# ABoatMon.net
KiCad netlist of a schematic drawn in EAGLE
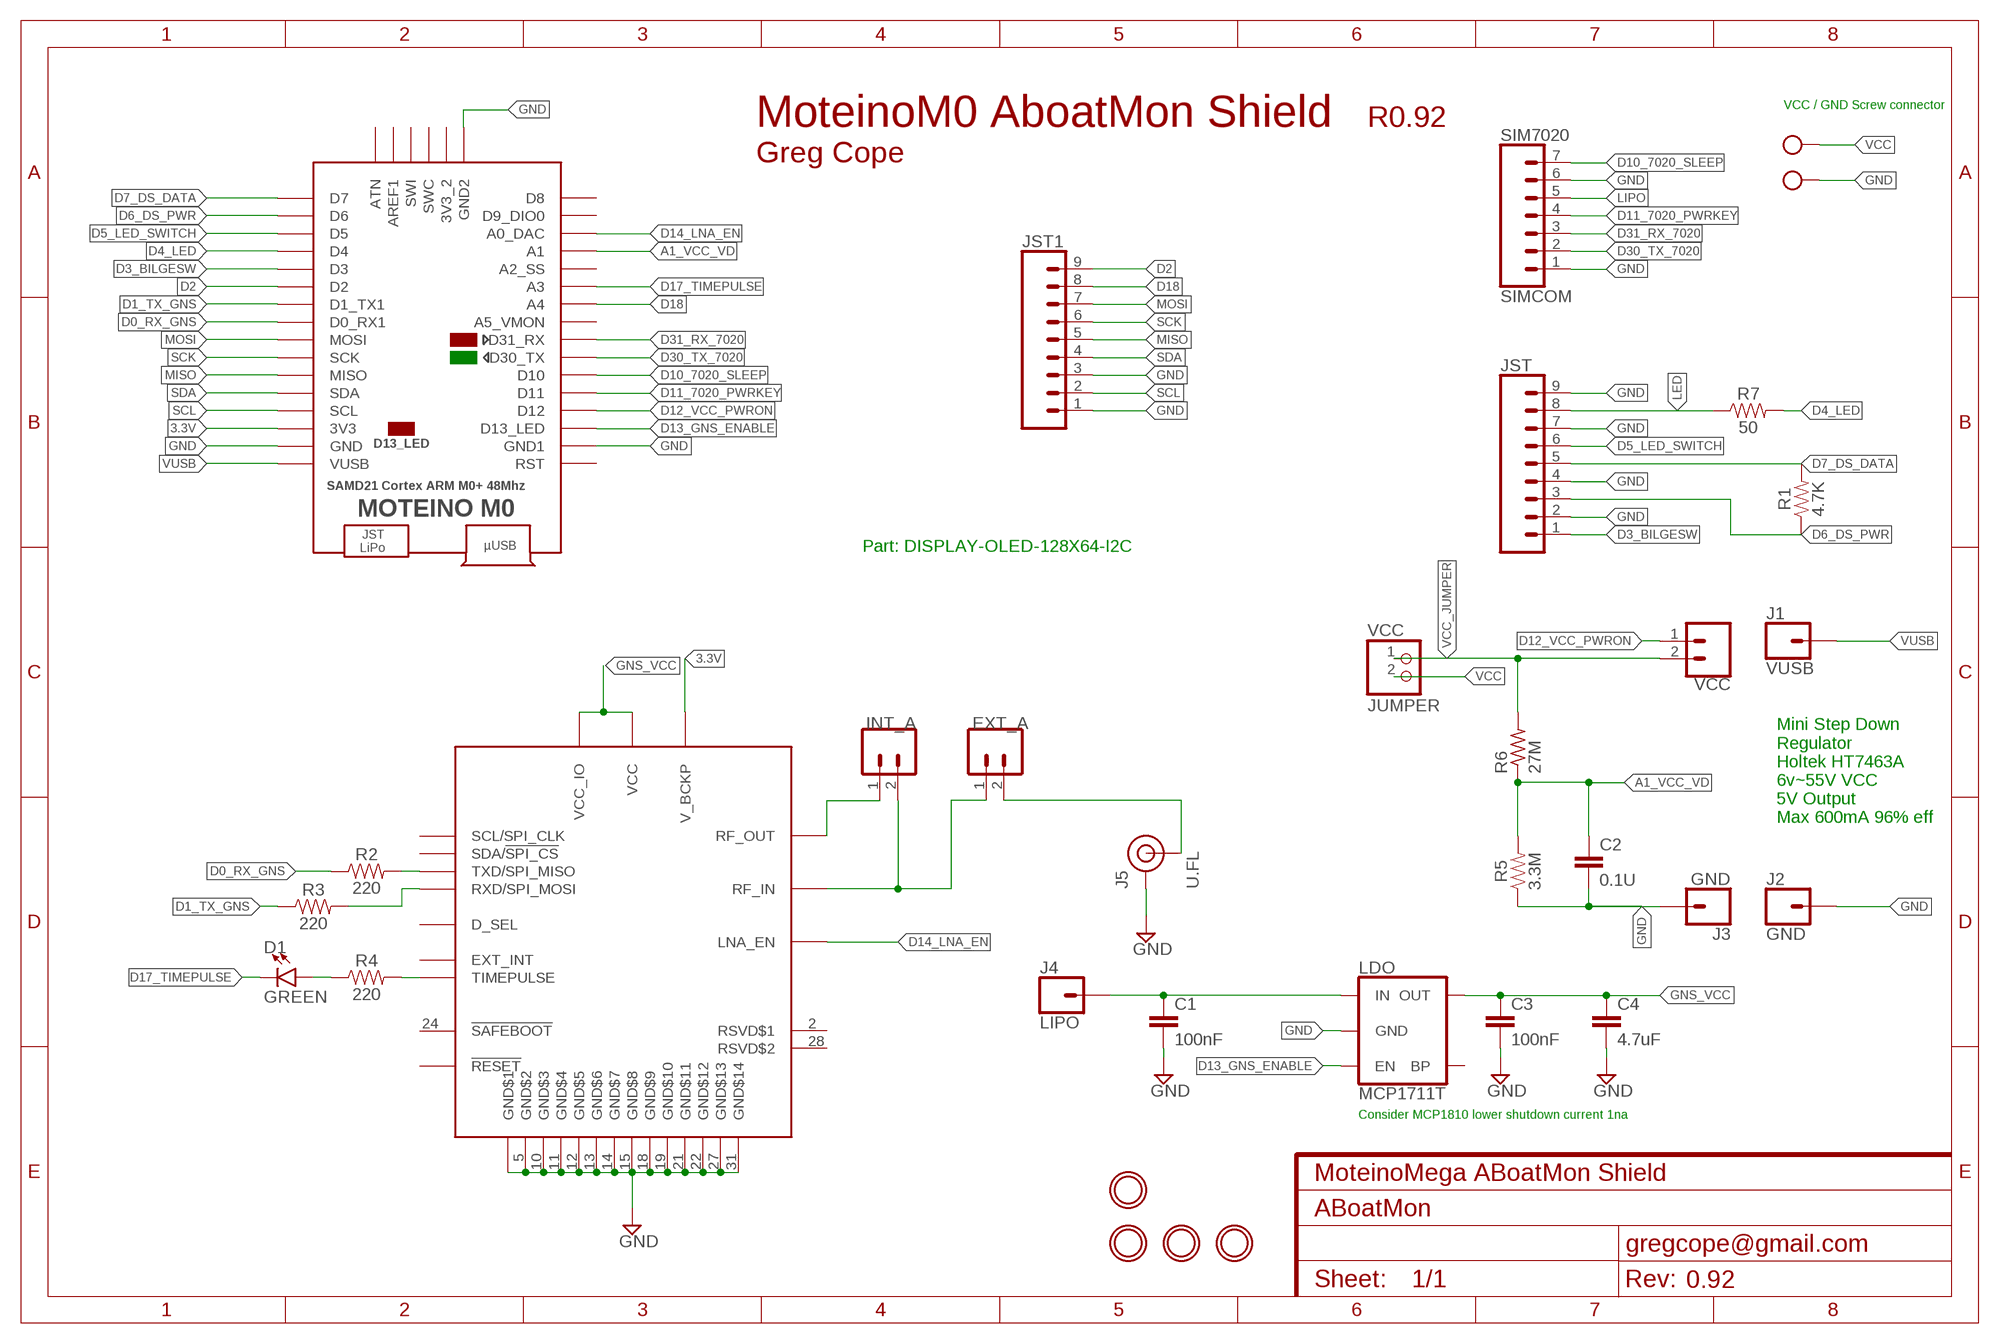
[diagram p0: schematic, sheet 1]

(export (version "E")
  (design (tool "Eeschema 10.0.6"))
  (components
    (comp (ref "C1")
      (value "100nF")
      (footprint "eagle-import:0603")
      (libsource (lib "eagle-import") (part "SparkFun-Capacitors_510_0.1UF-0603-25V-5%"))
    )
    (comp (ref "C2")
      (value "0.1U")
      (footprint "eagle-import:CAP-PTH-SMALL-KIT")
      (libsource (lib "eagle-import") (part "0.1UF-KIT-EZ-50V-20%"))
    )
    (comp (ref "C3")
      (value "100nF")
      (footprint "eagle-import:0603")
      (libsource (lib "eagle-import") (part "SparkFun-Capacitors_510_0.1UF-0603-25V-5%"))
    )
    (comp (ref "C4")
      (value "4.7uF")
      (footprint "eagle-import:0603")
      (libsource (lib "eagle-import") (part "4.7UF0603"))
    )
    (comp (ref "D1")
      (value "GREEN")
      (footprint "eagle-import:LED-0603")
      (libsource (lib "eagle-import") (part "LED-GREEN0603"))
    )
    (comp (ref "ENABLE")
      (value "VCC")
      (footprint "eagle-import:1X02")
      (libsource (lib "eagle-import") (part "CONN_02"))
    )
    (comp (ref "EXT_A")
      (value "CONN_02")
      (footprint "eagle-import:1X02")
      (libsource (lib "eagle-import") (part "SparkFun-Connectors_513_CONN_02"))
    )
    (comp (ref "GND")
      (value "MOUNTINGHOLE2.5")
      (footprint "eagle-import:MOUNTINGHOLE_2.5_PLATED")
      (libsource (lib "eagle-import") (part "MOUNTINGHOLE2.5"))
    )
    (comp (ref "INT_A")
      (value "CONN_02")
      (footprint "eagle-import:1X02")
      (libsource (lib "eagle-import") (part "SparkFun-Connectors_513_CONN_02"))
    )
    (comp (ref "J1")
      (value "VUSB")
      (footprint "eagle-import:1X01")
      (libsource (lib "eagle-import") (part "CONN_01"))
    )
    (comp (ref "J2")
      (value "GND")
      (footprint "eagle-import:1X01")
      (libsource (lib "eagle-import") (part "CONN_01"))
    )
    (comp (ref "J3")
      (value "GND")
      (footprint "eagle-import:1X01")
      (libsource (lib "eagle-import") (part "CONN_01"))
    )
    (comp (ref "J4")
      (value "LIPO")
      (footprint "eagle-import:1X01")
      (libsource (lib "eagle-import") (part "CONN_01"))
    )
    (comp (ref "J5")
      (value "U.FL")
      (footprint "eagle-import:U.FL")
      (libsource (lib "eagle-import") (part "U.FL2PIN"))
    )
    (comp (ref "JST")
      (value "CONN_09")
      (footprint "eagle-import:1X09")
      (libsource (lib "eagle-import") (part "CONN_09"))
    )
    (comp (ref "JST1")
      (value "CONN_09")
      (footprint "eagle-import:1X09")
      (libsource (lib "eagle-import") (part "CONN_09"))
    )
    (comp (ref "LDO")
      (value "MCP1711T")
      (footprint "eagle-import:SOT23-5")
      (libsource (lib "eagle-import") (part "V_REG_SPX3819-SOT23-5"))
    )
    (comp (ref "R1")
      (value "4.7K")
      (footprint "eagle-import:AXIAL-0.3")
      (libsource (lib "eagle-import") (part "1KOHM-HORIZ-1/4W-1%"))
    )
    (comp (ref "R2")
      (value "220")
      (footprint "eagle-import:0603")
      (libsource (lib "eagle-import") (part "220OHM-0603-1/10W-1%"))
    )
    (comp (ref "R3")
      (value "220")
      (footprint "eagle-import:0603")
      (libsource (lib "eagle-import") (part "220OHM-0603-1/10W-1%"))
    )
    (comp (ref "R4")
      (value "220")
      (footprint "eagle-import:0603")
      (libsource (lib "eagle-import") (part "220OHM-0603-1/10W-1%"))
    )
    (comp (ref "R5")
      (value "3.3M")
      (footprint "eagle-import:AXIAL-0.3")
      (libsource (lib "eagle-import") (part "1KOHM-HORIZ-1/4W-1%"))
    )
    (comp (ref "R6")
      (value "27M")
      (footprint "eagle-import:0309_12")
      (libsource (lib "eagle-import") (part "R-US_0309/12"))
    )
    (comp (ref "R7")
      (value "50")
      (footprint "eagle-import:AXIAL-0.3")
      (libsource (lib "eagle-import") (part "1KOHM-HORIZ-1/4W-1%"))
    )
    (comp (ref "SIM7020")
      (value "SIMCOM")
      (footprint "eagle-import:1X07")
      (libsource (lib "eagle-import") (part "CONN_07"))
    )
    (comp (ref "U$3")
      (value "MOUNTINGHOLE2.0")
      (footprint "eagle-import:MOUNTINGHOLE_2.0_PLATED")
      (libsource (lib "eagle-import") (part "MOUNTINGHOLE2.0"))
    )
    (comp (ref "U$5")
      (value "CAM-M8")
      (footprint "eagle-import:CAM-M8")
      (libsource (lib "eagle-import") (part "CAM-M8"))
    )
    (comp (ref "U$6")
      (value "MOTEINO_M0")
      (footprint "eagle-import:MOTEINO_M0")
      (libsource (lib "eagle-import") (part "MOTEINO_M0"))
    )
    (comp (ref "U$7")
      (value "MOUNTINGHOLE2.5")
      (footprint "eagle-import:MOUNTINGHOLE_2.5_PLATED")
      (libsource (lib "eagle-import") (part "MOUNTINGHOLE2.5"))
    )
    (comp (ref "U$9")
      (value "MOUNTINGHOLE2.0")
      (footprint "eagle-import:MOUNTINGHOLE_2.0_PLATED")
      (libsource (lib "eagle-import") (part "MOUNTINGHOLE2.0"))
    )
    (comp (ref "VCC")
      (value "JUMPER")
      (footprint "eagle-import:1X02_ROUND")
      (libsource (lib "eagle-import") (part "HEADER-1X2ROUND"))
    )
    (comp (ref "X1")
      (value "MKDSN1,5/2-5,08")
      (footprint "eagle-import:MKDSN1,5_2-5,08")
      (libsource (lib "eagle-import") (part "MKDSN1,5/2-5,08"))
    )
  )
  (nets
    (net (code "1") (name "3.3V") (class "Default")
      (node (ref "U$5") (pin "8") (pinfunction "V_BCKP_8") (pintype "power_in"))
      (node (ref "U$6") (pin "3V3") (pinfunction "3V3_3V3") (pintype "bidirectional"))
    )
    (net (code "2") (name "A1_VCC_VD") (class "Default")
      (node (ref "C2") (pin "1") (pinfunction "1_1") (pintype "passive"))
      (node (ref "R5") (pin "P$2") (pinfunction "2_P$2") (pintype "passive"))
      (node (ref "R6") (pin "1") (pinfunction "1_1") (pintype "passive"))
      (node (ref "U$6") (pin "A1") (pinfunction "A1_A1") (pintype "bidirectional"))
    )
    (net (code "3") (name "D0_RX_GNS") (class "Default")
      (node (ref "R2") (pin "1") (pinfunction "1_1") (pintype "passive"))
      (node (ref "U$6") (pin "D0_RX1") (pinfunction "D0_RX1_D0_RX1") (pintype "bidirectional"))
    )
    (net (code "4") (name "D1_TX_GNS") (class "Default")
      (node (ref "R3") (pin "1") (pinfunction "1_1") (pintype "passive"))
      (node (ref "U$6") (pin "D1_TX1") (pinfunction "D1_TX1_D1_TX1") (pintype "bidirectional"))
    )
    (net (code "5") (name "D2") (class "Default")
      (node (ref "JST1") (pin "9") (pinfunction "9_9") (pintype "passive"))
      (node (ref "U$6") (pin "D2") (pinfunction "D2_D2") (pintype "bidirectional"))
    )
    (net (code "6") (name "D3_BILGESW") (class "Default")
      (node (ref "JST") (pin "1") (pinfunction "1_1") (pintype "passive"))
      (node (ref "U$6") (pin "D3") (pinfunction "D3_D3") (pintype "bidirectional"))
    )
    (net (code "7") (name "D4_LED") (class "Default")
      (node (ref "R7") (pin "P$2") (pinfunction "2_P$2") (pintype "passive"))
      (node (ref "U$6") (pin "D4") (pinfunction "D4_D4") (pintype "bidirectional"))
    )
    (net (code "8") (name "D5_LED_SWITCH") (class "Default")
      (node (ref "JST") (pin "6") (pinfunction "6_6") (pintype "passive"))
      (node (ref "U$6") (pin "D5") (pinfunction "D5_D5") (pintype "bidirectional"))
    )
    (net (code "9") (name "D6_DS_PWR") (class "Default")
      (node (ref "JST") (pin "3") (pinfunction "3_3") (pintype "passive"))
      (node (ref "R1") (pin "P$1") (pinfunction "1_P$1") (pintype "passive"))
      (node (ref "U$6") (pin "D6") (pinfunction "D6_D6") (pintype "bidirectional"))
    )
    (net (code "10") (name "D7_DS_DATA") (class "Default")
      (node (ref "JST") (pin "5") (pinfunction "5_5") (pintype "passive"))
      (node (ref "R1") (pin "P$2") (pinfunction "2_P$2") (pintype "passive"))
      (node (ref "U$6") (pin "D7") (pinfunction "D7_D7") (pintype "bidirectional"))
    )
    (net (code "11") (name "D10_7020_SLEEP") (class "Default")
      (node (ref "SIM7020") (pin "7") (pinfunction "7_7") (pintype "passive"))
      (node (ref "U$6") (pin "D10") (pinfunction "D10_D10") (pintype "bidirectional"))
    )
    (net (code "12") (name "D11_7020_PWRKEY") (class "Default")
      (node (ref "SIM7020") (pin "4") (pinfunction "4_4") (pintype "passive"))
      (node (ref "U$6") (pin "D11") (pinfunction "D11_D11") (pintype "bidirectional"))
    )
    (net (code "13") (name "D12_VCC_PWRON") (class "Default")
      (node (ref "ENABLE") (pin "1") (pinfunction "1_1") (pintype "passive"))
      (node (ref "U$6") (pin "D12") (pinfunction "D12_D12") (pintype "bidirectional"))
    )
    (net (code "14") (name "D13_GNS_ENABLE") (class "Default")
      (node (ref "LDO") (pin "3") (pinfunction "EN_3") (pintype "input"))
      (node (ref "U$6") (pin "D13") (pinfunction "D13_LED_D13") (pintype "bidirectional"))
    )
    (net (code "15") (name "D14_LNA_EN") (class "Default")
      (node (ref "U$5") (pin "30") (pinfunction "LNA_EN_30") (pintype "output"))
      (node (ref "U$6") (pin "A0_DAC") (pinfunction "A0_DAC_A0_DAC") (pintype "bidirectional"))
    )
    (net (code "16") (name "D17_TIMEPULSE") (class "Default")
      (node (ref "D1") (pin "C") (pinfunction "C_C") (pintype "passive"))
      (node (ref "U$6") (pin "A3") (pinfunction "A3_A3") (pintype "bidirectional"))
    )
    (net (code "17") (name "D18") (class "Default")
      (node (ref "JST1") (pin "8") (pinfunction "8_8") (pintype "passive"))
      (node (ref "U$6") (pin "A4") (pinfunction "A4_A4") (pintype "bidirectional"))
    )
    (net (code "18") (name "D30_TX_7020") (class "Default")
      (node (ref "SIM7020") (pin "2") (pinfunction "2_2") (pintype "passive"))
      (node (ref "U$6") (pin "D30_TX") (pinfunction "D30_TX_D30_TX") (pintype "bidirectional"))
    )
    (net (code "19") (name "D31_RX_7020") (class "Default")
      (node (ref "SIM7020") (pin "3") (pinfunction "3_3") (pintype "passive"))
      (node (ref "U$6") (pin "D31_RX") (pinfunction "D31_RX_D31_RX") (pintype "bidirectional"))
    )
    (net (code "20") (name "GND") (class "Default")
      (node (ref "C1") (pin "2") (pinfunction "2_2") (pintype "passive"))
      (node (ref "C2") (pin "2") (pinfunction "2_2") (pintype "passive"))
      (node (ref "C3") (pin "2") (pinfunction "2_2") (pintype "passive"))
      (node (ref "C4") (pin "2") (pinfunction "2_2") (pintype "passive"))
      (node (ref "J2") (pin "1") (pinfunction "1_1") (pintype "passive"))
      (node (ref "J3") (pin "1") (pinfunction "1_1") (pintype "passive"))
      (node (ref "J5") (pin "1") (pinfunction "GND_1") (pintype "bidirectional"))
      (node (ref "J5") (pin "2") (pinfunction "GND_2") (pintype "bidirectional"))
      (node (ref "JST") (pin "2") (pinfunction "2_2") (pintype "passive"))
      (node (ref "JST") (pin "4") (pinfunction "4_4") (pintype "passive"))
      (node (ref "JST") (pin "7") (pinfunction "7_7") (pintype "passive"))
      (node (ref "JST") (pin "9") (pinfunction "9_9") (pintype "passive"))
      (node (ref "JST1") (pin "1") (pinfunction "1_1") (pintype "passive"))
      (node (ref "JST1") (pin "3") (pinfunction "3_3") (pintype "passive"))
      (node (ref "LDO") (pin "2") (pinfunction "GND_2") (pintype "input"))
      (node (ref "R5") (pin "P$1") (pinfunction "1_P$1") (pintype "passive"))
      (node (ref "SIM7020") (pin "1") (pinfunction "1_1") (pintype "passive"))
      (node (ref "SIM7020") (pin "6") (pinfunction "6_6") (pintype "passive"))
      (node (ref "U$5") (pin "10") (pinfunction "GND$3_10") (pintype "power_in"))
      (node (ref "U$5") (pin "11") (pinfunction "GND$4_11") (pintype "power_in"))
      (node (ref "U$5") (pin "12") (pinfunction "GND$5_12") (pintype "power_in"))
      (node (ref "U$5") (pin "13") (pinfunction "GND$6_13") (pintype "power_in"))
      (node (ref "U$5") (pin "14") (pinfunction "GND$7_14") (pintype "power_in"))
      (node (ref "U$5") (pin "15") (pinfunction "GND$8_15") (pintype "power_in"))
      (node (ref "U$5") (pin "18") (pinfunction "GND$9_18") (pintype "power_in"))
      (node (ref "U$5") (pin "19") (pinfunction "GND$10_19") (pintype "power_in"))
      (node (ref "U$5") (pin "21") (pinfunction "GND$11_21") (pintype "power_in"))
      (node (ref "U$5") (pin "22") (pinfunction "GND$12_22") (pintype "power_in"))
      (node (ref "U$5") (pin "27") (pinfunction "GND$13_27") (pintype "power_in"))
      (node (ref "U$5") (pin "31") (pinfunction "GND$14_31") (pintype "power_in"))
      (node (ref "U$5") (pin "4") (pinfunction "GND$1_4") (pintype "power_in"))
      (node (ref "U$5") (pin "5") (pinfunction "GND$2_5") (pintype "power_in"))
      (node (ref "U$6") (pin "GND") (pinfunction "GND_GND") (pintype "bidirectional"))
      (node (ref "U$6") (pin "GND_1") (pinfunction "GND1_GND_1") (pintype "bidirectional"))
      (node (ref "U$6") (pin "GND_2") (pinfunction "GND2_GND_2") (pintype "bidirectional"))
      (node (ref "X1") (pin "2") (pinfunction "KL_2") (pintype "passive"))
    )
    (net (code "21") (name "GNS_VCC") (class "Default")
      (node (ref "C3") (pin "1") (pinfunction "1_1") (pintype "passive"))
      (node (ref "C4") (pin "1") (pinfunction "1_1") (pintype "passive"))
      (node (ref "LDO") (pin "5") (pinfunction "OUT_5") (pintype "passive"))
      (node (ref "U$5") (pin "1") (pinfunction "VCC_IO_1") (pintype "power_in"))
      (node (ref "U$5") (pin "9") (pinfunction "VCC_9") (pintype "power_in"))
    )
    (net (code "22") (name "LED") (class "Default")
      (node (ref "JST") (pin "8") (pinfunction "8_8") (pintype "passive"))
      (node (ref "R7") (pin "P$1") (pinfunction "1_P$1") (pintype "passive"))
    )
    (net (code "23") (name "LIPO") (class "Default")
      (node (ref "C1") (pin "1") (pinfunction "1_1") (pintype "passive"))
      (node (ref "J4") (pin "1") (pinfunction "1_1") (pintype "passive"))
      (node (ref "LDO") (pin "1") (pinfunction "IN_1") (pintype "input"))
      (node (ref "SIM7020") (pin "5") (pinfunction "5_5") (pintype "passive"))
    )
    (net (code "24") (name "MISO") (class "Default")
      (node (ref "JST1") (pin "5") (pinfunction "5_5") (pintype "passive"))
      (node (ref "U$6") (pin "MISO") (pinfunction "MISO_MISO") (pintype "bidirectional"))
    )
    (net (code "25") (name "MOSI") (class "Default")
      (node (ref "JST1") (pin "7") (pinfunction "7_7") (pintype "passive"))
      (node (ref "U$6") (pin "MOSI") (pinfunction "MOSI_MOSI") (pintype "bidirectional"))
    )
    (net (code "26") (name "Net-(D1-PadA)") (class "Default")
      (node (ref "D1") (pin "A") (pinfunction "A_A") (pintype "passive"))
      (node (ref "R4") (pin "1") (pinfunction "1_1") (pintype "passive"))
    )
    (net (code "27") (name "Net-(J5-SIGNAL)") (class "Default")
      (node (ref "EXT_A") (pin "2") (pinfunction "2_2") (pintype "passive"))
      (node (ref "J5") (pin "FEED") (pinfunction "SIGNAL_FEED") (pintype "bidirectional"))
    )
    (net (code "28") (name "Net-(U$5-RF_IN)") (class "Default")
      (node (ref "EXT_A") (pin "1") (pinfunction "1_1") (pintype "passive"))
      (node (ref "INT_A") (pin "2") (pinfunction "2_2") (pintype "passive"))
      (node (ref "U$5") (pin "17") (pinfunction "RF_IN_17") (pintype "input"))
    )
    (net (code "29") (name "Net-(U$5-RF_OUT)") (class "Default")
      (node (ref "INT_A") (pin "1") (pinfunction "1_1") (pintype "passive"))
      (node (ref "U$5") (pin "16") (pinfunction "RF_OUT_16") (pintype "output"))
    )
    (net (code "30") (name "Net-(U$5-RXD{slash}SPI_MOSI)") (class "Default")
      (node (ref "R3") (pin "2") (pinfunction "2_2") (pintype "passive"))
      (node (ref "U$5") (pin "26") (pinfunction "RXD/SPI_MOSI_26") (pintype "input"))
    )
    (net (code "31") (name "Net-(U$5-TIMEPULSE)") (class "Default")
      (node (ref "R4") (pin "2") (pinfunction "2_2") (pintype "passive"))
      (node (ref "U$5") (pin "29") (pinfunction "TIMEPULSE_29") (pintype "output"))
    )
    (net (code "32") (name "Net-(U$5-TXD{slash}SPI_MISO)") (class "Default")
      (node (ref "R2") (pin "2") (pinfunction "2_2") (pintype "passive"))
      (node (ref "U$5") (pin "25") (pinfunction "TXD/SPI_MISO_25") (pintype "output"))
    )
    (net (code "33") (name "SCK") (class "Default")
      (node (ref "JST1") (pin "6") (pinfunction "6_6") (pintype "passive"))
      (node (ref "U$6") (pin "SCK") (pinfunction "SCK_SCK") (pintype "bidirectional"))
    )
    (net (code "34") (name "SCL") (class "Default")
      (node (ref "JST1") (pin "2") (pinfunction "2_2") (pintype "passive"))
      (node (ref "U$6") (pin "SCL") (pinfunction "SCL_SCL") (pintype "bidirectional"))
    )
    (net (code "35") (name "SDA") (class "Default")
      (node (ref "JST1") (pin "4") (pinfunction "4_4") (pintype "passive"))
      (node (ref "U$6") (pin "SDA") (pinfunction "SDA_SDA") (pintype "bidirectional"))
    )
    (net (code "36") (name "VCC") (class "Default")
      (node (ref "VCC") (pin "2") (pinfunction "2_2") (pintype "passive"))
      (node (ref "X1") (pin "1") (pinfunction "KL_1") (pintype "passive"))
    )
    (net (code "37") (name "VCC_JUMPER") (class "Default")
      (node (ref "ENABLE") (pin "2") (pinfunction "2_2") (pintype "passive"))
      (node (ref "R6") (pin "2") (pinfunction "2_2") (pintype "passive"))
      (node (ref "VCC") (pin "1") (pinfunction "1_1") (pintype "passive"))
    )
    (net (code "38") (name "VUSB") (class "Default")
      (node (ref "J1") (pin "1") (pinfunction "1_1") (pintype "passive"))
      (node (ref "U$6") (pin "VUSB") (pinfunction "VUSB_VUSB") (pintype "bidirectional"))
    )
    (net (code "39") (name "unconnected-(LDO-BP-Pad4)") (class "Default")
      (node (ref "LDO") (pin "4") (pinfunction "BP_4") (pintype "input"))
    )
    (net (code "40") (name "unconnected-(U$5-D_SEL-Pad20)") (class "Default")
      (node (ref "U$5") (pin "20") (pinfunction "D_SEL_20") (pintype "input"))
    )
    (net (code "41") (name "unconnected-(U$5-EXT_INT-Pad7)") (class "Default")
      (node (ref "U$5") (pin "7") (pinfunction "EXT_INT_7") (pintype "bidirectional"))
    )
    (net (code "42") (name "unconnected-(U$5-RSVD$1-Pad2)") (class "Default")
      (node (ref "U$5") (pin "2") (pinfunction "RSVD$1_2") (pintype "no_connect"))
    )
    (net (code "43") (name "unconnected-(U$5-RSVD$2-Pad28)") (class "Default")
      (node (ref "U$5") (pin "28") (pinfunction "RSVD$2_28") (pintype "no_connect"))
    )
    (net (code "44") (name "unconnected-(U$5-SCL{slash}SPI_CLK-Pad6)") (class "Default")
      (node (ref "U$5") (pin "6") (pinfunction "SCL/SPI_CLK_6") (pintype "input"))
    )
    (net (code "45") (name "unconnected-(U$5-SDA{slash}~{SPI_CS}-Pad3)") (class "Default")
      (node (ref "U$5") (pin "3") (pinfunction "SDA/~{SPI_CS}_3") (pintype "bidirectional"))
    )
    (net (code "46") (name "unconnected-(U$5-~{RESET}-Pad23)") (class "Default")
      (node (ref "U$5") (pin "23") (pinfunction "~{RESET}_23") (pintype "input"))
    )
    (net (code "47") (name "unconnected-(U$5-~{SAFEBOOT}-Pad24)") (class "Default")
      (node (ref "U$5") (pin "24") (pinfunction "~{SAFEBOOT}_24") (pintype "input"))
    )
    (net (code "48") (name "unconnected-(U$6-A2_SS-PadA2)") (class "Default")
      (node (ref "U$6") (pin "A2") (pinfunction "A2_SS_A2") (pintype "bidirectional"))
    )
    (net (code "49") (name "unconnected-(U$6-A5_VMON-PadA5)") (class "Default")
      (node (ref "U$6") (pin "A5") (pinfunction "A5_VMON_A5") (pintype "bidirectional"))
    )
    (net (code "50") (name "unconnected-(U$6-AREF1-PadAREF)") (class "Default")
      (node (ref "U$6") (pin "AREF") (pinfunction "AREF1_AREF") (pintype "bidirectional"))
    )
    (net (code "51") (name "unconnected-(U$6-D9_DIO0-PadD9)") (class "Default")
      (node (ref "U$6") (pin "D9") (pinfunction "D9_DIO0_D9") (pintype "bidirectional"))
    )
    (net (code "52") (name "unconnected-(U$6-Pad3V3_2)") (class "Default")
      (node (ref "U$6") (pin "3V3_2") (pinfunction "3V3_2_3V3_2") (pintype "bidirectional"))
    )
    (net (code "53") (name "unconnected-(U$6-PadATN)") (class "Default")
      (node (ref "U$6") (pin "ATN") (pinfunction "ATN_ATN") (pintype "bidirectional"))
    )
    (net (code "54") (name "unconnected-(U$6-PadD8)") (class "Default")
      (node (ref "U$6") (pin "D8") (pinfunction "D8_D8") (pintype "bidirectional"))
    )
    (net (code "55") (name "unconnected-(U$6-PadRST)") (class "Default")
      (node (ref "U$6") (pin "RST") (pinfunction "RST_RST") (pintype "bidirectional"))
    )
    (net (code "56") (name "unconnected-(U$6-PadSWC)") (class "Default")
      (node (ref "U$6") (pin "SWC") (pinfunction "SWC_SWC") (pintype "bidirectional"))
    )
    (net (code "57") (name "unconnected-(U$6-PadSWI)") (class "Default")
      (node (ref "U$6") (pin "SWI") (pinfunction "SWI_SWI") (pintype "bidirectional"))
    )
  )
)
